# PF2_AudioInput.net
KiCad netlist of a schematic drawn in Altium Designer
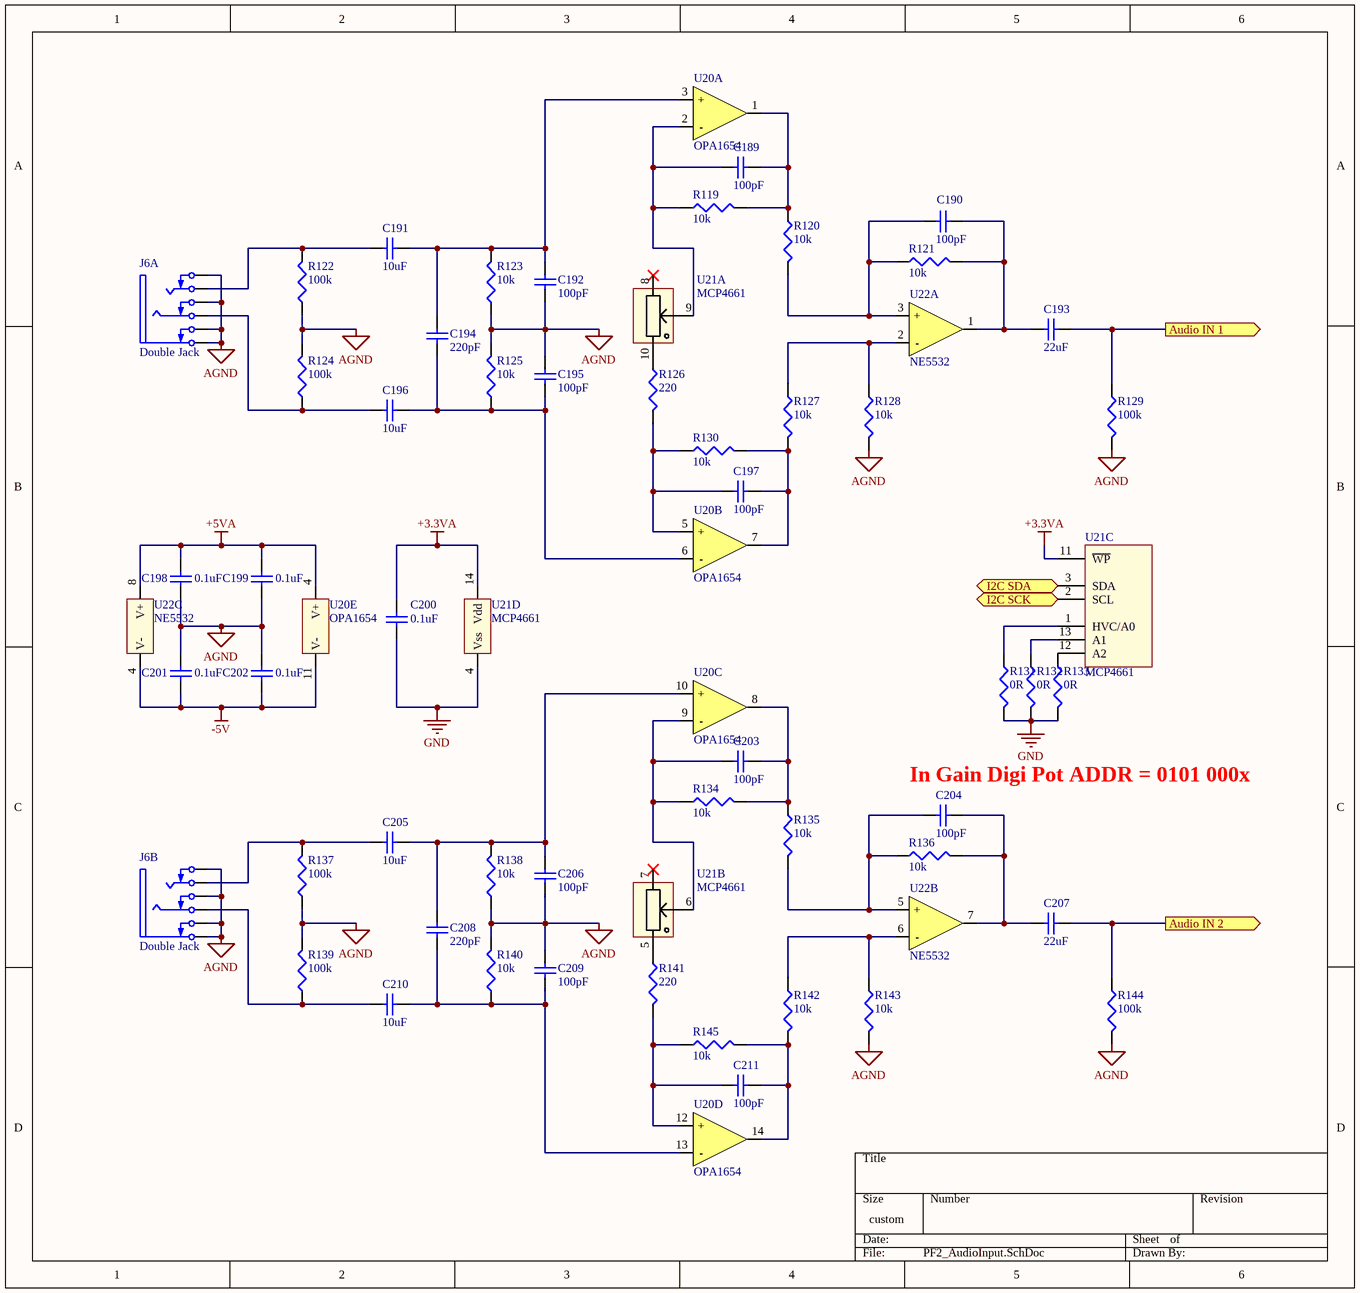
[diagram p0: PF2_AudioInput.SchDoc]

(export (version "E")
  (design (tool "Eeschema 10.0.6"))
  (components
    (comp (ref "C189")
      (value "100pF")
      (footprint "CAPC1608X08")
      (description "Capacitor (Semiconductor SIM Model)")
      (libsource (lib "Michel") (part "Cap Semi"))
    )
    (comp (ref "C190")
      (value "100pF")
      (footprint "CAPC1608X08")
      (description "Capacitor (Semiconductor SIM Model)")
      (libsource (lib "Michel") (part "Cap Semi"))
    )
    (comp (ref "C191")
      (value "10uF")
      (footprint "CAPC1608X08")
      (description "Capacitor (Semiconductor SIM Model)")
      (libsource (lib "Michel") (part "Cap Semi"))
    )
    (comp (ref "C192")
      (value "100pF")
      (footprint "CAPC1608X08")
      (description "Capacitor (Semiconductor SIM Model)")
      (libsource (lib "Michel") (part "Cap Semi"))
    )
    (comp (ref "C193")
      (value "22uF")
      (footprint "CAPC1608X08")
      (description "Capacitor (Semiconductor SIM Model)")
      (libsource (lib "Michel") (part "Cap Semi"))
    )
    (comp (ref "C194")
      (value "220pF")
      (footprint "CAPC1608X08")
      (description "Capacitor (Semiconductor SIM Model)")
      (libsource (lib "Michel") (part "Cap Semi"))
    )
    (comp (ref "C195")
      (value "100pF")
      (footprint "CAPC1608X08")
      (description "Capacitor (Semiconductor SIM Model)")
      (libsource (lib "Michel") (part "Cap Semi"))
    )
    (comp (ref "C196")
      (value "10uF")
      (footprint "CAPC1608X08")
      (description "Capacitor (Semiconductor SIM Model)")
      (libsource (lib "Michel") (part "Cap Semi"))
    )
    (comp (ref "C197")
      (value "100pF")
      (footprint "CAPC1608X08")
      (description "Capacitor (Semiconductor SIM Model)")
      (libsource (lib "Michel") (part "Cap Semi"))
    )
    (comp (ref "C198")
      (value "0.1uF")
      (footprint "CAPC1608X08")
      (description "Capacitor (Semiconductor SIM Model)")
      (libsource (lib "Michel") (part "Cap Semi"))
    )
    (comp (ref "C199")
      (value "0.1uF")
      (footprint "CAPC1608X08")
      (description "Capacitor (Semiconductor SIM Model)")
      (libsource (lib "Michel") (part "Cap Semi"))
    )
    (comp (ref "C200")
      (value "0.1uF")
      (footprint "CAPC1608X08")
      (description "Capacitor (Semiconductor SIM Model)")
      (libsource (lib "Michel") (part "Cap Semi"))
    )
    (comp (ref "C201")
      (value "0.1uF")
      (footprint "CAPC1608X08")
      (description "Capacitor (Semiconductor SIM Model)")
      (libsource (lib "Michel") (part "Cap Semi"))
    )
    (comp (ref "C202")
      (value "0.1uF")
      (footprint "CAPC1608X08")
      (description "Capacitor (Semiconductor SIM Model)")
      (libsource (lib "Michel") (part "Cap Semi"))
    )
    (comp (ref "C203")
      (value "100pF")
      (footprint "CAPC1608X08")
      (description "Capacitor (Semiconductor SIM Model)")
      (libsource (lib "Michel") (part "Cap Semi"))
    )
    (comp (ref "C204")
      (value "100pF")
      (footprint "CAPC1608X08")
      (description "Capacitor (Semiconductor SIM Model)")
      (libsource (lib "Michel") (part "Cap Semi"))
    )
    (comp (ref "C205")
      (value "10uF")
      (footprint "CAPC1608X08")
      (description "Capacitor (Semiconductor SIM Model)")
      (libsource (lib "Michel") (part "Cap Semi"))
    )
    (comp (ref "C206")
      (value "100pF")
      (footprint "CAPC1608X08")
      (description "Capacitor (Semiconductor SIM Model)")
      (libsource (lib "Michel") (part "Cap Semi"))
    )
    (comp (ref "C207")
      (value "22uF")
      (footprint "CAPC1608X08")
      (description "Capacitor (Semiconductor SIM Model)")
      (libsource (lib "Michel") (part "Cap Semi"))
    )
    (comp (ref "C208")
      (value "220pF")
      (footprint "CAPC1608X08")
      (description "Capacitor (Semiconductor SIM Model)")
      (libsource (lib "Michel") (part "Cap Semi"))
    )
    (comp (ref "C209")
      (value "100pF")
      (footprint "CAPC1608X08")
      (description "Capacitor (Semiconductor SIM Model)")
      (libsource (lib "Michel") (part "Cap Semi"))
    )
    (comp (ref "C210")
      (value "10uF")
      (footprint "CAPC1608X08")
      (description "Capacitor (Semiconductor SIM Model)")
      (libsource (lib "Michel") (part "Cap Semi"))
    )
    (comp (ref "C211")
      (value "100pF")
      (footprint "CAPC1608X08")
      (description "Capacitor (Semiconductor SIM Model)")
      (libsource (lib "Michel") (part "Cap Semi"))
    )
    (comp (ref "J6")
      (value "Double Jack")
      (footprint "Amphenol_ACJS-MHDC")
      (description "Dual Jack stereo bypassed")
      (libsource (lib "Michel") (part "Dual TRS Jack Bypassed"))
    )
    (comp (ref "R119")
      (value "10k")
      (footprint "RESC1608X05")
      (description "Resistor")
      (libsource (lib "Michel") (part "Res3"))
    )
    (comp (ref "R120")
      (value "10k")
      (footprint "RESC1608X05")
      (description "Resistor")
      (libsource (lib "Michel") (part "Res3"))
    )
    (comp (ref "R121")
      (value "10k")
      (footprint "RESC1608X05")
      (description "Resistor")
      (libsource (lib "Michel") (part "Res3"))
    )
    (comp (ref "R122")
      (value "100k")
      (footprint "RESC1608X05")
      (description "Resistor")
      (libsource (lib "Michel") (part "Res3"))
    )
    (comp (ref "R123")
      (value "10k")
      (footprint "RESC1608X05")
      (description "Resistor")
      (libsource (lib "Michel") (part "Res3"))
    )
    (comp (ref "R124")
      (value "100k")
      (footprint "RESC1608X05")
      (description "Resistor")
      (libsource (lib "Michel") (part "Res3"))
    )
    (comp (ref "R125")
      (value "10k")
      (footprint "RESC1608X05")
      (description "Resistor")
      (libsource (lib "Michel") (part "Res3"))
    )
    (comp (ref "R126")
      (value "220")
      (footprint "RESC1608X05")
      (description "Resistor")
      (libsource (lib "Michel") (part "Res3"))
    )
    (comp (ref "R127")
      (value "10k")
      (footprint "RESC1608X05")
      (description "Resistor")
      (libsource (lib "Michel") (part "Res3"))
    )
    (comp (ref "R128")
      (value "10k")
      (footprint "RESC1608X05")
      (description "Resistor")
      (libsource (lib "Michel") (part "Res3"))
    )
    (comp (ref "R129")
      (value "100k")
      (footprint "RESC1608X05")
      (description "Resistor")
      (libsource (lib "Michel") (part "Res3"))
    )
    (comp (ref "R130")
      (value "10k")
      (footprint "RESC1608X05")
      (description "Resistor")
      (libsource (lib "Michel") (part "Res3"))
    )
    (comp (ref "R131")
      (value "0R")
      (footprint "RESC1608X05")
      (description "Resistor")
      (libsource (lib "Michel") (part "Res3"))
    )
    (comp (ref "R132")
      (value "0R")
      (footprint "RESC1608X05")
      (description "Resistor")
      (libsource (lib "Michel") (part "Res3"))
    )
    (comp (ref "R133")
      (value "0R")
      (footprint "RESC1608X05")
      (description "Resistor")
      (libsource (lib "Michel") (part "Res3"))
    )
    (comp (ref "R134")
      (value "10k")
      (footprint "RESC1608X05")
      (description "Resistor")
      (libsource (lib "Michel") (part "Res3"))
    )
    (comp (ref "R135")
      (value "10k")
      (footprint "RESC1608X05")
      (description "Resistor")
      (libsource (lib "Michel") (part "Res3"))
    )
    (comp (ref "R136")
      (value "10k")
      (footprint "RESC1608X05")
      (description "Resistor")
      (libsource (lib "Michel") (part "Res3"))
    )
    (comp (ref "R137")
      (value "100k")
      (footprint "RESC1608X05")
      (description "Resistor")
      (libsource (lib "Michel") (part "Res3"))
    )
    (comp (ref "R138")
      (value "10k")
      (footprint "RESC1608X05")
      (description "Resistor")
      (libsource (lib "Michel") (part "Res3"))
    )
    (comp (ref "R139")
      (value "100k")
      (footprint "RESC1608X05")
      (description "Resistor")
      (libsource (lib "Michel") (part "Res3"))
    )
    (comp (ref "R140")
      (value "10k")
      (footprint "RESC1608X05")
      (description "Resistor")
      (libsource (lib "Michel") (part "Res3"))
    )
    (comp (ref "R141")
      (value "220")
      (footprint "RESC1608X05")
      (description "Resistor")
      (libsource (lib "Michel") (part "Res3"))
    )
    (comp (ref "R142")
      (value "10k")
      (footprint "RESC1608X05")
      (description "Resistor")
      (libsource (lib "Michel") (part "Res3"))
    )
    (comp (ref "R143")
      (value "10k")
      (footprint "RESC1608X05")
      (description "Resistor")
      (libsource (lib "Michel") (part "Res3"))
    )
    (comp (ref "R144")
      (value "100k")
      (footprint "RESC1608X05")
      (description "Resistor")
      (libsource (lib "Michel") (part "Res3"))
    )
    (comp (ref "R145")
      (value "10k")
      (footprint "RESC1608X05")
      (description "Resistor")
      (libsource (lib "Michel") (part "Res3"))
    )
    (comp (ref "U20")
      (value "OPA1654")
      (footprint "D14-M")
      (description "Quad Audio OpAmp")
      (libsource (lib "Michel") (part "OPA1654"))
    )
    (comp (ref "U21")
      (value "MCP4661")
      (footprint "TSSOP14_MC-M")
      (description "Dual DigiPot non volatile I2C")
      (libsource (lib "Michel") (part "MCP4661"))
    )
    (comp (ref "U22")
      (value "NE5532")
      (footprint "D8-M")
      (description "Dual Audio OpAmp")
      (libsource (lib "Michel") (part "NE5532"))
    )
  )
  (nets
    (net (code "1") (name "+3.3VA") (class "Default")
      (node (ref "C200") (pin "1") (pinfunction "1_1") (pintype "passive"))
      (node (ref "U21") (pin "11") (pinfunction "~{WP}_11") (pintype "passive"))
      (node (ref "U21") (pin "14") (pinfunction "Vdd_14") (pintype "power_in"))
    )
    (net (code "2") (name "+5VA") (class "Default")
      (node (ref "C198") (pin "1") (pinfunction "1_1") (pintype "passive"))
      (node (ref "C199") (pin "1") (pinfunction "1_1") (pintype "passive"))
      (node (ref "U20") (pin "4") (pinfunction "V+_4") (pintype "power_in"))
      (node (ref "U22") (pin "8") (pinfunction "V+_8") (pintype "power_in"))
    )
    (net (code "3") (name "-5V") (class "Default")
      (node (ref "C201") (pin "2") (pinfunction "2_2") (pintype "passive"))
      (node (ref "C202") (pin "2") (pinfunction "2_2") (pintype "passive"))
      (node (ref "U20") (pin "11") (pinfunction "V-_11") (pintype "power_in"))
      (node (ref "U22") (pin "4") (pinfunction "V-_4") (pintype "power_in"))
    )
    (net (code "4") (name "/Audio IN 1") (class "Default")
      (node (ref "C193") (pin "1") (pinfunction "1_1") (pintype "passive"))
      (node (ref "R129") (pin "1") (pinfunction "1_1") (pintype "passive"))
    )
    (net (code "5") (name "/Audio IN 2") (class "Default")
      (node (ref "C207") (pin "1") (pinfunction "1_1") (pintype "passive"))
      (node (ref "R144") (pin "1") (pinfunction "1_1") (pintype "passive"))
    )
    (net (code "6") (name "/I2C SCK") (class "Default")
      (node (ref "U21") (pin "2") (pinfunction "SCL_2") (pintype "passive"))
    )
    (net (code "7") (name "/I2C SDA") (class "Default")
      (node (ref "U21") (pin "3") (pinfunction "SDA_3") (pintype "passive"))
    )
    (net (code "8") (name "AGND") (class "Default")
      (node (ref "C192") (pin "2") (pinfunction "2_2") (pintype "passive"))
      (node (ref "C195") (pin "1") (pinfunction "1_1") (pintype "passive"))
      (node (ref "C198") (pin "2") (pinfunction "2_2") (pintype "passive"))
      (node (ref "C199") (pin "2") (pinfunction "2_2") (pintype "passive"))
      (node (ref "C201") (pin "1") (pinfunction "1_1") (pintype "passive"))
      (node (ref "C202") (pin "1") (pinfunction "1_1") (pintype "passive"))
      (node (ref "C206") (pin "2") (pinfunction "2_2") (pintype "passive"))
      (node (ref "C209") (pin "1") (pinfunction "1_1") (pintype "passive"))
      (node (ref "J6") (pin "1") (pinfunction "SB_1") (pintype "passive"))
      (node (ref "J6") (pin "10") (pinfunction "S_10") (pintype "power_in"))
      (node (ref "J6") (pin "2") (pinfunction "RB_2") (pintype "passive"))
      (node (ref "J6") (pin "3") (pinfunction "TB_3") (pintype "passive"))
      (node (ref "J6") (pin "4") (pinfunction "S_4") (pintype "power_in"))
      (node (ref "J6") (pin "7") (pinfunction "SB_7") (pintype "passive"))
      (node (ref "J6") (pin "8") (pinfunction "RB_8") (pintype "passive"))
      (node (ref "J6") (pin "9") (pinfunction "TB_9") (pintype "passive"))
      (node (ref "R122") (pin "1") (pinfunction "1_1") (pintype "passive"))
      (node (ref "R123") (pin "1") (pinfunction "1_1") (pintype "passive"))
      (node (ref "R124") (pin "2") (pinfunction "2_2") (pintype "passive"))
      (node (ref "R125") (pin "2") (pinfunction "2_2") (pintype "passive"))
      (node (ref "R128") (pin "2") (pinfunction "2_2") (pintype "passive"))
      (node (ref "R129") (pin "2") (pinfunction "2_2") (pintype "passive"))
      (node (ref "R137") (pin "1") (pinfunction "1_1") (pintype "passive"))
      (node (ref "R138") (pin "1") (pinfunction "1_1") (pintype "passive"))
      (node (ref "R139") (pin "2") (pinfunction "2_2") (pintype "passive"))
      (node (ref "R140") (pin "2") (pinfunction "2_2") (pintype "passive"))
      (node (ref "R143") (pin "2") (pinfunction "2_2") (pintype "passive"))
      (node (ref "R144") (pin "2") (pinfunction "2_2") (pintype "passive"))
    )
    (net (code "9") (name "GND") (class "Default")
      (node (ref "C200") (pin "2") (pinfunction "2_2") (pintype "passive"))
      (node (ref "R131") (pin "2") (pinfunction "2_2") (pintype "passive"))
      (node (ref "R132") (pin "2") (pinfunction "2_2") (pintype "passive"))
      (node (ref "R133") (pin "2") (pinfunction "2_2") (pintype "passive"))
      (node (ref "U21") (pin "4") (pinfunction "Vss_4") (pintype "power_in"))
    )
    (net (code "10") (name "Net-(J6A-R)") (class "Default")
      (node (ref "C196") (pin "2") (pinfunction "2_2") (pintype "passive"))
      (node (ref "J6") (pin "11") (pinfunction "R_11") (pintype "passive"))
      (node (ref "R124") (pin "1") (pinfunction "1_1") (pintype "passive"))
    )
    (net (code "11") (name "Net-(J6A-T)") (class "Default")
      (node (ref "C191") (pin "2") (pinfunction "2_2") (pintype "passive"))
      (node (ref "J6") (pin "12") (pinfunction "T_12") (pintype "passive"))
      (node (ref "R122") (pin "2") (pinfunction "2_2") (pintype "passive"))
    )
    (net (code "12") (name "Net-(J6B-R)") (class "Default")
      (node (ref "C210") (pin "2") (pinfunction "2_2") (pintype "passive"))
      (node (ref "J6") (pin "5") (pinfunction "R_5") (pintype "passive"))
      (node (ref "R139") (pin "1") (pinfunction "1_1") (pintype "passive"))
    )
    (net (code "13") (name "Net-(J6B-T)") (class "Default")
      (node (ref "C205") (pin "2") (pinfunction "2_2") (pintype "passive"))
      (node (ref "J6") (pin "6") (pinfunction "T_6") (pintype "passive"))
      (node (ref "R137") (pin "2") (pinfunction "2_2") (pintype "passive"))
    )
    (net (code "14") (name "Net-(U20A-+)") (class "Default")
      (node (ref "C191") (pin "1") (pinfunction "1_1") (pintype "passive"))
      (node (ref "C192") (pin "1") (pinfunction "1_1") (pintype "passive"))
      (node (ref "C194") (pin "1") (pinfunction "1_1") (pintype "passive"))
      (node (ref "R123") (pin "2") (pinfunction "2_2") (pintype "passive"))
      (node (ref "U20") (pin "3") (pinfunction "+_3") (pintype "passive"))
    )
    (net (code "15") (name "Net-(U20A--)") (class "Default")
      (node (ref "C189") (pin "1") (pinfunction "1_1") (pintype "passive"))
      (node (ref "R119") (pin "1") (pinfunction "1_1") (pintype "passive"))
      (node (ref "U20") (pin "2") (pinfunction "-_2") (pintype "passive"))
      (node (ref "U21") (pin "9") (pinfunction "P0W_9") (pintype "passive"))
    )
    (net (code "16") (name "Net-(U20A-OUT)") (class "Default")
      (node (ref "C189") (pin "2") (pinfunction "2_2") (pintype "passive"))
      (node (ref "R119") (pin "2") (pinfunction "2_2") (pintype "passive"))
      (node (ref "R120") (pin "1") (pinfunction "1_1") (pintype "passive"))
      (node (ref "U20") (pin "1") (pinfunction "OUT_1") (pintype "passive"))
    )
    (net (code "17") (name "Net-(U20B-+)") (class "Default")
      (node (ref "C197") (pin "1") (pinfunction "1_1") (pintype "passive"))
      (node (ref "R126") (pin "2") (pinfunction "2_2") (pintype "passive"))
      (node (ref "R130") (pin "1") (pinfunction "1_1") (pintype "passive"))
      (node (ref "U20") (pin "5") (pinfunction "+_5") (pintype "passive"))
    )
    (net (code "18") (name "Net-(U20B--)") (class "Default")
      (node (ref "C194") (pin "2") (pinfunction "2_2") (pintype "passive"))
      (node (ref "C195") (pin "2") (pinfunction "2_2") (pintype "passive"))
      (node (ref "C196") (pin "1") (pinfunction "1_1") (pintype "passive"))
      (node (ref "R125") (pin "1") (pinfunction "1_1") (pintype "passive"))
      (node (ref "U20") (pin "6") (pinfunction "-_6") (pintype "passive"))
    )
    (net (code "19") (name "Net-(U20B-OUT)") (class "Default")
      (node (ref "C197") (pin "2") (pinfunction "2_2") (pintype "passive"))
      (node (ref "R127") (pin "2") (pinfunction "2_2") (pintype "passive"))
      (node (ref "R130") (pin "2") (pinfunction "2_2") (pintype "passive"))
      (node (ref "U20") (pin "7") (pinfunction "OUT_7") (pintype "passive"))
    )
    (net (code "20") (name "Net-(U20C-+)") (class "Default")
      (node (ref "C205") (pin "1") (pinfunction "1_1") (pintype "passive"))
      (node (ref "C206") (pin "1") (pinfunction "1_1") (pintype "passive"))
      (node (ref "C208") (pin "1") (pinfunction "1_1") (pintype "passive"))
      (node (ref "R138") (pin "2") (pinfunction "2_2") (pintype "passive"))
      (node (ref "U20") (pin "10") (pinfunction "+_10") (pintype "passive"))
    )
    (net (code "21") (name "Net-(U20C--)") (class "Default")
      (node (ref "C203") (pin "1") (pinfunction "1_1") (pintype "passive"))
      (node (ref "R134") (pin "1") (pinfunction "1_1") (pintype "passive"))
      (node (ref "U20") (pin "9") (pinfunction "-_9") (pintype "passive"))
      (node (ref "U21") (pin "6") (pinfunction "P1W_6") (pintype "passive"))
    )
    (net (code "22") (name "Net-(U20C-OUT)") (class "Default")
      (node (ref "C203") (pin "2") (pinfunction "2_2") (pintype "passive"))
      (node (ref "R134") (pin "2") (pinfunction "2_2") (pintype "passive"))
      (node (ref "R135") (pin "1") (pinfunction "1_1") (pintype "passive"))
      (node (ref "U20") (pin "8") (pinfunction "OUT_8") (pintype "passive"))
    )
    (net (code "23") (name "Net-(U20D-+)") (class "Default")
      (node (ref "C211") (pin "1") (pinfunction "1_1") (pintype "passive"))
      (node (ref "R141") (pin "2") (pinfunction "2_2") (pintype "passive"))
      (node (ref "R145") (pin "1") (pinfunction "1_1") (pintype "passive"))
      (node (ref "U20") (pin "12") (pinfunction "+_12") (pintype "passive"))
    )
    (net (code "24") (name "Net-(U20D--)") (class "Default")
      (node (ref "C208") (pin "2") (pinfunction "2_2") (pintype "passive"))
      (node (ref "C209") (pin "2") (pinfunction "2_2") (pintype "passive"))
      (node (ref "C210") (pin "1") (pinfunction "1_1") (pintype "passive"))
      (node (ref "R140") (pin "1") (pinfunction "1_1") (pintype "passive"))
      (node (ref "U20") (pin "13") (pinfunction "-_13") (pintype "passive"))
    )
    (net (code "25") (name "Net-(U20D-OUT)") (class "Default")
      (node (ref "C211") (pin "2") (pinfunction "2_2") (pintype "passive"))
      (node (ref "R142") (pin "2") (pinfunction "2_2") (pintype "passive"))
      (node (ref "R145") (pin "2") (pinfunction "2_2") (pintype "passive"))
      (node (ref "U20") (pin "14") (pinfunction "OUT_14") (pintype "passive"))
    )
    (net (code "26") (name "Net-(U21A-P0B)") (class "Default")
      (node (ref "R126") (pin "1") (pinfunction "1_1") (pintype "passive"))
      (node (ref "U21") (pin "10") (pinfunction "P0B_10") (pintype "passive"))
    )
    (net (code "27") (name "Net-(U21B-P1B)") (class "Default")
      (node (ref "R141") (pin "1") (pinfunction "1_1") (pintype "passive"))
      (node (ref "U21") (pin "5") (pinfunction "P1B_5") (pintype "passive"))
    )
    (net (code "28") (name "Net-(U21C-A1)") (class "Default")
      (node (ref "R132") (pin "1") (pinfunction "1_1") (pintype "passive"))
      (node (ref "U21") (pin "13") (pinfunction "A1_13") (pintype "power_in"))
    )
    (net (code "29") (name "Net-(U21C-A2)") (class "Default")
      (node (ref "R133") (pin "1") (pinfunction "1_1") (pintype "passive"))
      (node (ref "U21") (pin "12") (pinfunction "A2_12") (pintype "power_in"))
    )
    (net (code "30") (name "Net-(U21C-HVC{slash}A0)") (class "Default")
      (node (ref "R131") (pin "1") (pinfunction "1_1") (pintype "passive"))
      (node (ref "U21") (pin "1") (pinfunction "HVC/A0_1") (pintype "power_in"))
    )
    (net (code "31") (name "Net-(U22A-+)") (class "Default")
      (node (ref "C190") (pin "1") (pinfunction "1_1") (pintype "passive"))
      (node (ref "R120") (pin "2") (pinfunction "2_2") (pintype "passive"))
      (node (ref "R121") (pin "1") (pinfunction "1_1") (pintype "passive"))
      (node (ref "U22") (pin "3") (pinfunction "+_3") (pintype "passive"))
    )
    (net (code "32") (name "Net-(U22A--)") (class "Default")
      (node (ref "R127") (pin "1") (pinfunction "1_1") (pintype "passive"))
      (node (ref "R128") (pin "1") (pinfunction "1_1") (pintype "passive"))
      (node (ref "U22") (pin "2") (pinfunction "-_2") (pintype "passive"))
    )
    (net (code "33") (name "Net-(U22A-OUT)") (class "Default")
      (node (ref "C190") (pin "2") (pinfunction "2_2") (pintype "passive"))
      (node (ref "C193") (pin "2") (pinfunction "2_2") (pintype "passive"))
      (node (ref "R121") (pin "2") (pinfunction "2_2") (pintype "passive"))
      (node (ref "U22") (pin "1") (pinfunction "OUT_1") (pintype "passive"))
    )
    (net (code "34") (name "Net-(U22B-+)") (class "Default")
      (node (ref "C204") (pin "1") (pinfunction "1_1") (pintype "passive"))
      (node (ref "R135") (pin "2") (pinfunction "2_2") (pintype "passive"))
      (node (ref "R136") (pin "1") (pinfunction "1_1") (pintype "passive"))
      (node (ref "U22") (pin "5") (pinfunction "+_5") (pintype "passive"))
    )
    (net (code "35") (name "Net-(U22B--)") (class "Default")
      (node (ref "R142") (pin "1") (pinfunction "1_1") (pintype "passive"))
      (node (ref "R143") (pin "1") (pinfunction "1_1") (pintype "passive"))
      (node (ref "U22") (pin "6") (pinfunction "-_6") (pintype "passive"))
    )
    (net (code "36") (name "Net-(U22B-OUT)") (class "Default")
      (node (ref "C204") (pin "2") (pinfunction "2_2") (pintype "passive"))
      (node (ref "C207") (pin "2") (pinfunction "2_2") (pintype "passive"))
      (node (ref "R136") (pin "2") (pinfunction "2_2") (pintype "passive"))
      (node (ref "U22") (pin "7") (pinfunction "OUT_7") (pintype "passive"))
    )
    (net (code "37") (name "unconnected-(U21A-P0A-Pad8)") (class "Default")
      (node (ref "U21") (pin "8") (pinfunction "P0A_8") (pintype "passive+no_connect"))
    )
    (net (code "38") (name "unconnected-(U21B-P1A-Pad7)") (class "Default")
      (node (ref "U21") (pin "7") (pinfunction "P1A_7") (pintype "passive+no_connect"))
    )
  )
)
